# bluetoothbm20breakout.net
KiCad netlist of a schematic drawn in EAGLE
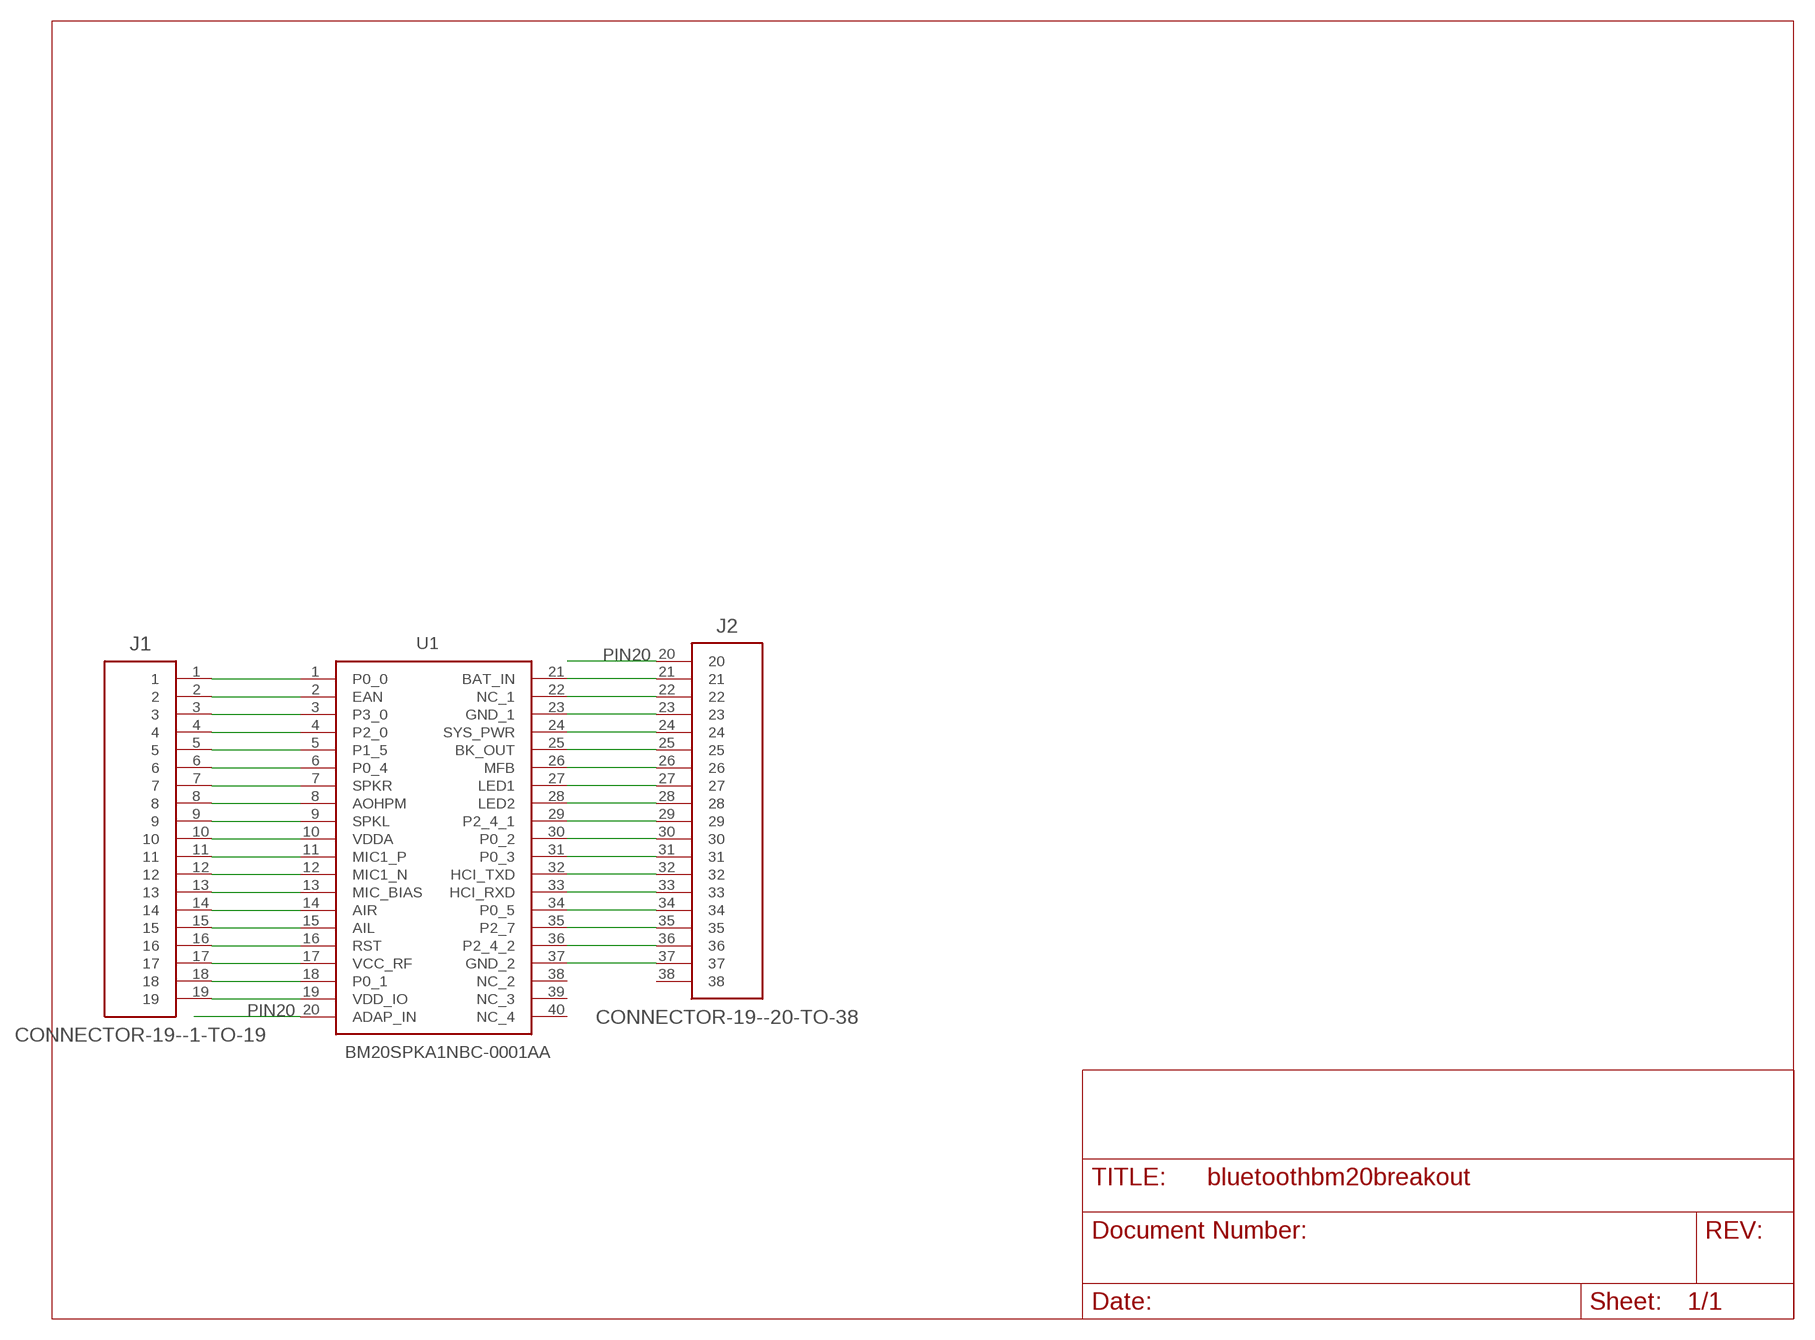
[diagram p0: schematic, sheet 1]

(export (version "E")
  (design (tool "Eeschema 10.0.6"))
  (components
    (comp (ref "J1")
      (value "CONNECTOR-19--1-TO-19")
      (footprint "eagle-import:ESQ-119-XX-XX-S")
      (libsource (lib "eagle-import") (part "CONNECTOR-19--1-TO-19"))
    )
    (comp (ref "J2")
      (value "CONNECTOR-19--20-TO-38")
      (footprint "eagle-import:ESQ-119-XX-XX-S--PIN-1-ROUND")
      (libsource (lib "eagle-import") (part "CONNECTOR-19--20-TO-38"))
    )
    (comp (ref "U1")
      (value "BM20SPKA1NBC-0001AA")
      (footprint "eagle-import:BM20SPKA1NBC0001AA")
      (fields (field (name "MOUSER_PART_NUMBER") "579-SPKA1NBC-0001AA"))
      (libsource (lib "eagle-import") (part "BM20SPKA1NBC-0001AA"))
    )
  )
  (nets
    (net (code "1") (name "/PIN20") (class "Default")
      (node (ref "J2") (pin "20") (pinfunction "20_20") (pintype "bidirectional"))
      (node (ref "U1") (pin "20") (pinfunction "ADAP_IN_20") (pintype "bidirectional"))
    )
    (net (code "2") (name "Net-(U1-AIL)") (class "Default")
      (node (ref "J1") (pin "15") (pinfunction "15_15") (pintype "bidirectional"))
      (node (ref "U1") (pin "15") (pinfunction "AIL_15") (pintype "bidirectional"))
    )
    (net (code "3") (name "Net-(U1-AIR)") (class "Default")
      (node (ref "J1") (pin "14") (pinfunction "14_14") (pintype "bidirectional"))
      (node (ref "U1") (pin "14") (pinfunction "AIR_14") (pintype "bidirectional"))
    )
    (net (code "4") (name "Net-(U1-AOHPM)") (class "Default")
      (node (ref "J1") (pin "8") (pinfunction "8_8") (pintype "bidirectional"))
      (node (ref "U1") (pin "8") (pinfunction "AOHPM_8") (pintype "bidirectional"))
    )
    (net (code "5") (name "Net-(U1-BAT_IN)") (class "Default")
      (node (ref "J2") (pin "21") (pinfunction "21_21") (pintype "bidirectional"))
      (node (ref "U1") (pin "21") (pinfunction "BAT_IN_21") (pintype "bidirectional"))
    )
    (net (code "6") (name "Net-(U1-BK_OUT)") (class "Default")
      (node (ref "J2") (pin "25") (pinfunction "25_25") (pintype "bidirectional"))
      (node (ref "U1") (pin "25") (pinfunction "BK_OUT_25") (pintype "bidirectional"))
    )
    (net (code "7") (name "Net-(U1-EAN)") (class "Default")
      (node (ref "J1") (pin "2") (pinfunction "2_2") (pintype "bidirectional"))
      (node (ref "U1") (pin "2") (pinfunction "EAN_2") (pintype "bidirectional"))
    )
    (net (code "8") (name "Net-(U1-GND_1)") (class "Default")
      (node (ref "J2") (pin "23") (pinfunction "23_23") (pintype "bidirectional"))
      (node (ref "U1") (pin "23") (pinfunction "GND_1_23") (pintype "bidirectional"))
    )
    (net (code "9") (name "Net-(U1-GND_2)") (class "Default")
      (node (ref "J2") (pin "37") (pinfunction "37_37") (pintype "bidirectional"))
      (node (ref "U1") (pin "37") (pinfunction "GND_2_37") (pintype "bidirectional"))
    )
    (net (code "10") (name "Net-(U1-HCI_RXD)") (class "Default")
      (node (ref "J2") (pin "33") (pinfunction "33_33") (pintype "bidirectional"))
      (node (ref "U1") (pin "33") (pinfunction "HCI_RXD_33") (pintype "bidirectional"))
    )
    (net (code "11") (name "Net-(U1-HCI_TXD)") (class "Default")
      (node (ref "J2") (pin "32") (pinfunction "32_32") (pintype "bidirectional"))
      (node (ref "U1") (pin "32") (pinfunction "HCI_TXD_32") (pintype "bidirectional"))
    )
    (net (code "12") (name "Net-(U1-LED1)") (class "Default")
      (node (ref "J2") (pin "27") (pinfunction "27_27") (pintype "bidirectional"))
      (node (ref "U1") (pin "27") (pinfunction "LED1_27") (pintype "bidirectional"))
    )
    (net (code "13") (name "Net-(U1-LED2)") (class "Default")
      (node (ref "J2") (pin "28") (pinfunction "28_28") (pintype "bidirectional"))
      (node (ref "U1") (pin "28") (pinfunction "LED2_28") (pintype "bidirectional"))
    )
    (net (code "14") (name "Net-(U1-MFB)") (class "Default")
      (node (ref "J2") (pin "26") (pinfunction "26_26") (pintype "bidirectional"))
      (node (ref "U1") (pin "26") (pinfunction "MFB_26") (pintype "bidirectional"))
    )
    (net (code "15") (name "Net-(U1-MIC1_N)") (class "Default")
      (node (ref "J1") (pin "12") (pinfunction "12_12") (pintype "bidirectional"))
      (node (ref "U1") (pin "12") (pinfunction "MIC1_N_12") (pintype "bidirectional"))
    )
    (net (code "16") (name "Net-(U1-MIC1_P)") (class "Default")
      (node (ref "J1") (pin "11") (pinfunction "11_11") (pintype "bidirectional"))
      (node (ref "U1") (pin "11") (pinfunction "MIC1_P_11") (pintype "bidirectional"))
    )
    (net (code "17") (name "Net-(U1-MIC_BIAS)") (class "Default")
      (node (ref "J1") (pin "13") (pinfunction "13_13") (pintype "bidirectional"))
      (node (ref "U1") (pin "13") (pinfunction "MIC_BIAS_13") (pintype "bidirectional"))
    )
    (net (code "18") (name "Net-(U1-NC_1)") (class "Default")
      (node (ref "J2") (pin "22") (pinfunction "22_22") (pintype "bidirectional"))
      (node (ref "U1") (pin "22") (pinfunction "NC_1_22") (pintype "bidirectional"))
    )
    (net (code "19") (name "Net-(U1-P0_0)") (class "Default")
      (node (ref "J1") (pin "1") (pinfunction "1_1") (pintype "bidirectional"))
      (node (ref "U1") (pin "1") (pinfunction "P0_0_1") (pintype "bidirectional"))
    )
    (net (code "20") (name "Net-(U1-P0_1)") (class "Default")
      (node (ref "J1") (pin "18") (pinfunction "18_18") (pintype "bidirectional"))
      (node (ref "U1") (pin "18") (pinfunction "P0_1_18") (pintype "bidirectional"))
    )
    (net (code "21") (name "Net-(U1-P0_2)") (class "Default")
      (node (ref "J2") (pin "30") (pinfunction "30_30") (pintype "bidirectional"))
      (node (ref "U1") (pin "30") (pinfunction "P0_2_30") (pintype "bidirectional"))
    )
    (net (code "22") (name "Net-(U1-P0_3)") (class "Default")
      (node (ref "J2") (pin "31") (pinfunction "31_31") (pintype "bidirectional"))
      (node (ref "U1") (pin "31") (pinfunction "P0_3_31") (pintype "bidirectional"))
    )
    (net (code "23") (name "Net-(U1-P0_4)") (class "Default")
      (node (ref "J1") (pin "6") (pinfunction "6_6") (pintype "bidirectional"))
      (node (ref "U1") (pin "6") (pinfunction "P0_4_6") (pintype "bidirectional"))
    )
    (net (code "24") (name "Net-(U1-P0_5)") (class "Default")
      (node (ref "J2") (pin "34") (pinfunction "34_34") (pintype "bidirectional"))
      (node (ref "U1") (pin "34") (pinfunction "P0_5_34") (pintype "bidirectional"))
    )
    (net (code "25") (name "Net-(U1-P1_5)") (class "Default")
      (node (ref "J1") (pin "5") (pinfunction "5_5") (pintype "bidirectional"))
      (node (ref "U1") (pin "5") (pinfunction "P1_5_5") (pintype "bidirectional"))
    )
    (net (code "26") (name "Net-(U1-P2_0)") (class "Default")
      (node (ref "J1") (pin "4") (pinfunction "4_4") (pintype "bidirectional"))
      (node (ref "U1") (pin "4") (pinfunction "P2_0_4") (pintype "bidirectional"))
    )
    (net (code "27") (name "Net-(U1-P2_4_1)") (class "Default")
      (node (ref "J2") (pin "29") (pinfunction "29_29") (pintype "bidirectional"))
      (node (ref "U1") (pin "29") (pinfunction "P2_4_1_29") (pintype "bidirectional"))
    )
    (net (code "28") (name "Net-(U1-P2_4_2)") (class "Default")
      (node (ref "J2") (pin "36") (pinfunction "36_36") (pintype "bidirectional"))
      (node (ref "U1") (pin "36") (pinfunction "P2_4_2_36") (pintype "bidirectional"))
    )
    (net (code "29") (name "Net-(U1-P2_7)") (class "Default")
      (node (ref "J2") (pin "35") (pinfunction "35_35") (pintype "bidirectional"))
      (node (ref "U1") (pin "35") (pinfunction "P2_7_35") (pintype "bidirectional"))
    )
    (net (code "30") (name "Net-(U1-P3_0)") (class "Default")
      (node (ref "J1") (pin "3") (pinfunction "3_3") (pintype "bidirectional"))
      (node (ref "U1") (pin "3") (pinfunction "P3_0_3") (pintype "bidirectional"))
    )
    (net (code "31") (name "Net-(U1-RST)") (class "Default")
      (node (ref "J1") (pin "16") (pinfunction "16_16") (pintype "bidirectional"))
      (node (ref "U1") (pin "16") (pinfunction "RST_16") (pintype "bidirectional"))
    )
    (net (code "32") (name "Net-(U1-SPKL)") (class "Default")
      (node (ref "J1") (pin "9") (pinfunction "9_9") (pintype "bidirectional"))
      (node (ref "U1") (pin "9") (pinfunction "SPKL_9") (pintype "bidirectional"))
    )
    (net (code "33") (name "Net-(U1-SPKR)") (class "Default")
      (node (ref "J1") (pin "7") (pinfunction "7_7") (pintype "bidirectional"))
      (node (ref "U1") (pin "7") (pinfunction "SPKR_7") (pintype "bidirectional"))
    )
    (net (code "34") (name "Net-(U1-SYS_PWR)") (class "Default")
      (node (ref "J2") (pin "24") (pinfunction "24_24") (pintype "bidirectional"))
      (node (ref "U1") (pin "24") (pinfunction "SYS_PWR_24") (pintype "bidirectional"))
    )
    (net (code "35") (name "Net-(U1-VCC_RF)") (class "Default")
      (node (ref "J1") (pin "17") (pinfunction "17_17") (pintype "bidirectional"))
      (node (ref "U1") (pin "17") (pinfunction "VCC_RF_17") (pintype "bidirectional"))
    )
    (net (code "36") (name "Net-(U1-VDDA)") (class "Default")
      (node (ref "J1") (pin "10") (pinfunction "10_10") (pintype "bidirectional"))
      (node (ref "U1") (pin "10") (pinfunction "VDDA_10") (pintype "bidirectional"))
    )
    (net (code "37") (name "Net-(U1-VDD_IO)") (class "Default")
      (node (ref "J1") (pin "19") (pinfunction "19_19") (pintype "bidirectional"))
      (node (ref "U1") (pin "19") (pinfunction "VDD_IO_19") (pintype "bidirectional"))
    )
    (net (code "38") (name "unconnected-(J2-Pad38)") (class "Default")
      (node (ref "J2") (pin "38") (pinfunction "38_38") (pintype "bidirectional"))
    )
    (net (code "39") (name "unconnected-(U1-NC_2-Pad38)") (class "Default")
      (node (ref "U1") (pin "38") (pinfunction "NC_2_38") (pintype "bidirectional"))
    )
    (net (code "40") (name "unconnected-(U1-NC_3-Pad39)") (class "Default")
      (node (ref "U1") (pin "39") (pinfunction "NC_3_39") (pintype "bidirectional"))
    )
    (net (code "41") (name "unconnected-(U1-NC_4-Pad40)") (class "Default")
      (node (ref "U1") (pin "40") (pinfunction "NC_4_40") (pintype "bidirectional"))
    )
  )
)
